# H_Bridge_AON6500.net
KiCad netlist of a schematic drawn in Altium Designer
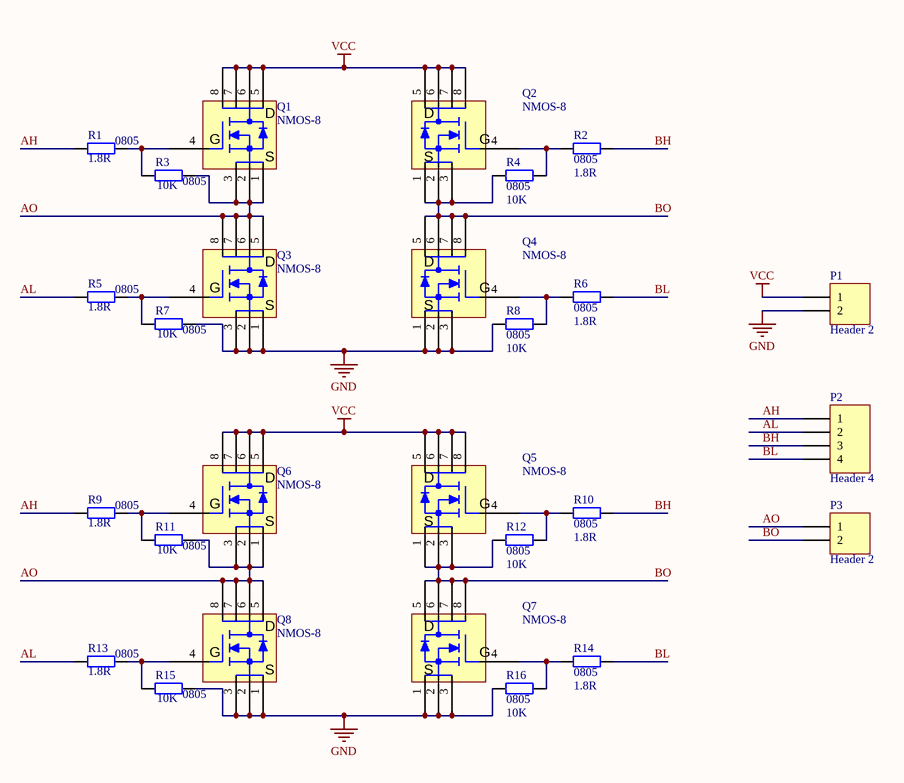
[diagram p0: H_Bridge_AON6500.SchDoc]

(export (version "E")
  (design (tool "Eeschema 10.0.6"))
  (components
    (comp (ref "P1")
      (value "Header 2")
      (footprint "HDR2.54-LI-2P")
      (description "Header, 2-Pin")
      (fields (field (name "PUBLISHER") "Altium Limited"))
      (libsource (lib "QT") (part "Header 2"))
    )
    (comp (ref "P2")
      (value "Header 4")
      (footprint "HDR2.54-LI-4P")
      (description "Header, 4-Pin")
      (fields (field (name "PUBLISHER") "Altium Limited"))
      (libsource (lib "QT") (part "Header 4"))
    )
    (comp (ref "P3")
      (value "Header 2")
      (footprint "HDR2.54-LI-2P")
      (description "Header, 2-Pin")
      (fields (field (name "PUBLISHER") "Altium Limited"))
      (libsource (lib "QT") (part "Header 2"))
    )
    (comp (ref "Q1") (value "NMOS-8") (footprint "PSOP8") (libsource (lib "") (part "NMOS-8_1")))
    (comp (ref "Q2") (value "NMOS-8") (footprint "PSOP8") (libsource (lib "常用元件库") (part "NMOS-8")))
    (comp (ref "Q3") (value "NMOS-8") (footprint "PSOP8") (libsource (lib "") (part "NMOS-8_1")))
    (comp (ref "Q4") (value "NMOS-8") (footprint "PSOP8") (libsource (lib "常用元件库") (part "NMOS-8")))
    (comp (ref "Q5") (value "NMOS-8") (footprint "PSOP8") (libsource (lib "常用元件库") (part "NMOS-8")))
    (comp (ref "Q6") (value "NMOS-8") (footprint "PSOP8") (libsource (lib "") (part "NMOS-8_1")))
    (comp (ref "Q7") (value "NMOS-8") (footprint "PSOP8") (libsource (lib "常用元件库") (part "NMOS-8")))
    (comp (ref "Q8") (value "NMOS-8") (footprint "PSOP8") (libsource (lib "") (part "NMOS-8_1")))
    (comp (ref "R1")
      (value "0805")
      (footprint "R 0805_L")
      (description "Resistor")
      (fields (field (name "ALTIUM_VALUE") "1.8R") (field (name "PUBLISHER") "Altium Limited"))
      (libsource (lib "QT") (part "RES2"))
    )
    (comp (ref "R2")
      (value "0805")
      (footprint "R 0805_L")
      (description "Resistor")
      (fields (field (name "ALTIUM_VALUE") "1.8R") (field (name "PUBLISHER") "Altium Limited"))
      (libsource (lib "") (part "RES2_1"))
    )
    (comp (ref "R3")
      (value "0805")
      (footprint "R 0805_L")
      (description "Resistor")
      (fields (field (name "ALTIUM_VALUE") "10K") (field (name "PUBLISHER") "Altium Limited"))
      (libsource (lib "QT") (part "RES2"))
    )
    (comp (ref "R4")
      (value "0805")
      (footprint "R 0805_L")
      (description "Resistor")
      (fields (field (name "ALTIUM_VALUE") "10K") (field (name "PUBLISHER") "Altium Limited"))
      (libsource (lib "") (part "RES2_1"))
    )
    (comp (ref "R5")
      (value "0805")
      (footprint "R 0805_L")
      (description "Resistor")
      (fields (field (name "ALTIUM_VALUE") "1.8R") (field (name "PUBLISHER") "Altium Limited"))
      (libsource (lib "QT") (part "RES2"))
    )
    (comp (ref "R6")
      (value "0805")
      (footprint "R 0805_L")
      (description "Resistor")
      (fields (field (name "ALTIUM_VALUE") "1.8R") (field (name "PUBLISHER") "Altium Limited"))
      (libsource (lib "") (part "RES2_1"))
    )
    (comp (ref "R7")
      (value "0805")
      (footprint "R 0805_L")
      (description "Resistor")
      (fields (field (name "ALTIUM_VALUE") "10K") (field (name "PUBLISHER") "Altium Limited"))
      (libsource (lib "QT") (part "RES2"))
    )
    (comp (ref "R8")
      (value "0805")
      (footprint "R 0805_L")
      (description "Resistor")
      (fields (field (name "ALTIUM_VALUE") "10K") (field (name "PUBLISHER") "Altium Limited"))
      (libsource (lib "") (part "RES2_1"))
    )
    (comp (ref "R9")
      (value "0805")
      (footprint "R 0805_L")
      (description "Resistor")
      (fields (field (name "ALTIUM_VALUE") "1.8R") (field (name "PUBLISHER") "Altium Limited"))
      (libsource (lib "QT") (part "RES2"))
    )
    (comp (ref "R10")
      (value "0805")
      (footprint "R 0805_L")
      (description "Resistor")
      (fields (field (name "ALTIUM_VALUE") "1.8R") (field (name "PUBLISHER") "Altium Limited"))
      (libsource (lib "") (part "RES2_1"))
    )
    (comp (ref "R11")
      (value "0805")
      (footprint "R 0805_L")
      (description "Resistor")
      (fields (field (name "ALTIUM_VALUE") "10K") (field (name "PUBLISHER") "Altium Limited"))
      (libsource (lib "QT") (part "RES2"))
    )
    (comp (ref "R12")
      (value "0805")
      (footprint "R 0805_L")
      (description "Resistor")
      (fields (field (name "ALTIUM_VALUE") "10K") (field (name "PUBLISHER") "Altium Limited"))
      (libsource (lib "") (part "RES2_1"))
    )
    (comp (ref "R13")
      (value "0805")
      (footprint "R 0805_L")
      (description "Resistor")
      (fields (field (name "ALTIUM_VALUE") "1.8R") (field (name "PUBLISHER") "Altium Limited"))
      (libsource (lib "QT") (part "RES2"))
    )
    (comp (ref "R14")
      (value "0805")
      (footprint "R 0805_L")
      (description "Resistor")
      (fields (field (name "ALTIUM_VALUE") "1.8R") (field (name "PUBLISHER") "Altium Limited"))
      (libsource (lib "") (part "RES2_1"))
    )
    (comp (ref "R15")
      (value "0805")
      (footprint "R 0805_L")
      (description "Resistor")
      (fields (field (name "ALTIUM_VALUE") "10K") (field (name "PUBLISHER") "Altium Limited"))
      (libsource (lib "QT") (part "RES2"))
    )
    (comp (ref "R16")
      (value "0805")
      (footprint "R 0805_L")
      (description "Resistor")
      (fields (field (name "ALTIUM_VALUE") "10K") (field (name "PUBLISHER") "Altium Limited"))
      (libsource (lib "") (part "RES2_1"))
    )
  )
  (nets
    (net (code "1") (name "/AH") (class "Default")
      (node (ref "P2") (pin "1") (pinfunction "1_1") (pintype "passive"))
      (node (ref "R1") (pin "1") (pinfunction "1_1") (pintype "passive"))
      (node (ref "R9") (pin "1") (pinfunction "1_1") (pintype "passive"))
    )
    (net (code "2") (name "/AL") (class "Default")
      (node (ref "P2") (pin "2") (pinfunction "2_2") (pintype "passive"))
      (node (ref "R13") (pin "1") (pinfunction "1_1") (pintype "passive"))
      (node (ref "R5") (pin "1") (pinfunction "1_1") (pintype "passive"))
    )
    (net (code "3") (name "/AO") (class "Default")
      (node (ref "P3") (pin "1") (pinfunction "1_1") (pintype "passive"))
      (node (ref "Q1") (pin "1") (pinfunction "S_1") (pintype "passive"))
      (node (ref "Q1") (pin "2") (pinfunction "S_2") (pintype "passive"))
      (node (ref "Q1") (pin "3") (pinfunction "S_3") (pintype "passive"))
      (node (ref "Q3") (pin "5") (pinfunction "5_5") (pintype "passive"))
      (node (ref "Q3") (pin "6") (pinfunction "6_6") (pintype "passive"))
      (node (ref "Q3") (pin "7") (pinfunction "7_7") (pintype "passive"))
      (node (ref "Q3") (pin "8") (pinfunction "8_8") (pintype "passive"))
      (node (ref "Q6") (pin "1") (pinfunction "S_1") (pintype "passive"))
      (node (ref "Q6") (pin "2") (pinfunction "S_2") (pintype "passive"))
      (node (ref "Q6") (pin "3") (pinfunction "S_3") (pintype "passive"))
      (node (ref "Q8") (pin "5") (pinfunction "5_5") (pintype "passive"))
      (node (ref "Q8") (pin "6") (pinfunction "6_6") (pintype "passive"))
      (node (ref "Q8") (pin "7") (pinfunction "7_7") (pintype "passive"))
      (node (ref "Q8") (pin "8") (pinfunction "8_8") (pintype "passive"))
      (node (ref "R11") (pin "2") (pinfunction "2_2") (pintype "passive"))
      (node (ref "R3") (pin "2") (pinfunction "2_2") (pintype "passive"))
    )
    (net (code "4") (name "/BH") (class "Default")
      (node (ref "P2") (pin "3") (pinfunction "3_3") (pintype "passive"))
      (node (ref "R10") (pin "1") (pinfunction "1_1") (pintype "passive"))
      (node (ref "R2") (pin "1") (pinfunction "1_1") (pintype "passive"))
    )
    (net (code "5") (name "/BL") (class "Default")
      (node (ref "P2") (pin "4") (pinfunction "4_4") (pintype "passive"))
      (node (ref "R14") (pin "1") (pinfunction "1_1") (pintype "passive"))
      (node (ref "R6") (pin "1") (pinfunction "1_1") (pintype "passive"))
    )
    (net (code "6") (name "/BO") (class "Default")
      (node (ref "P3") (pin "2") (pinfunction "2_2") (pintype "passive"))
      (node (ref "Q2") (pin "1") (pinfunction "S_1") (pintype "passive"))
      (node (ref "Q2") (pin "2") (pinfunction "S_2") (pintype "passive"))
      (node (ref "Q2") (pin "3") (pinfunction "S_3") (pintype "passive"))
      (node (ref "Q4") (pin "5") (pinfunction "5_5") (pintype "passive"))
      (node (ref "Q4") (pin "6") (pinfunction "6_6") (pintype "passive"))
      (node (ref "Q4") (pin "7") (pinfunction "7_7") (pintype "passive"))
      (node (ref "Q4") (pin "8") (pinfunction "8_8") (pintype "passive"))
      (node (ref "Q5") (pin "1") (pinfunction "S_1") (pintype "passive"))
      (node (ref "Q5") (pin "2") (pinfunction "S_2") (pintype "passive"))
      (node (ref "Q5") (pin "3") (pinfunction "S_3") (pintype "passive"))
      (node (ref "Q7") (pin "5") (pinfunction "5_5") (pintype "passive"))
      (node (ref "Q7") (pin "6") (pinfunction "6_6") (pintype "passive"))
      (node (ref "Q7") (pin "7") (pinfunction "7_7") (pintype "passive"))
      (node (ref "Q7") (pin "8") (pinfunction "8_8") (pintype "passive"))
      (node (ref "R12") (pin "2") (pinfunction "2_2") (pintype "passive"))
      (node (ref "R4") (pin "2") (pinfunction "2_2") (pintype "passive"))
    )
    (net (code "7") (name "GND") (class "Default")
      (node (ref "P1") (pin "2") (pinfunction "2_2") (pintype "passive"))
      (node (ref "Q3") (pin "1") (pinfunction "S_1") (pintype "passive"))
      (node (ref "Q3") (pin "2") (pinfunction "S_2") (pintype "passive"))
      (node (ref "Q3") (pin "3") (pinfunction "S_3") (pintype "passive"))
      (node (ref "Q4") (pin "1") (pinfunction "S_1") (pintype "passive"))
      (node (ref "Q4") (pin "2") (pinfunction "S_2") (pintype "passive"))
      (node (ref "Q4") (pin "3") (pinfunction "S_3") (pintype "passive"))
      (node (ref "Q7") (pin "1") (pinfunction "S_1") (pintype "passive"))
      (node (ref "Q7") (pin "2") (pinfunction "S_2") (pintype "passive"))
      (node (ref "Q7") (pin "3") (pinfunction "S_3") (pintype "passive"))
      (node (ref "Q8") (pin "1") (pinfunction "S_1") (pintype "passive"))
      (node (ref "Q8") (pin "2") (pinfunction "S_2") (pintype "passive"))
      (node (ref "Q8") (pin "3") (pinfunction "S_3") (pintype "passive"))
      (node (ref "R15") (pin "2") (pinfunction "2_2") (pintype "passive"))
      (node (ref "R16") (pin "2") (pinfunction "2_2") (pintype "passive"))
      (node (ref "R7") (pin "2") (pinfunction "2_2") (pintype "passive"))
      (node (ref "R8") (pin "2") (pinfunction "2_2") (pintype "passive"))
    )
    (net (code "8") (name "Net-(Q1-G)") (class "Default")
      (node (ref "Q1") (pin "4") (pinfunction "G_4") (pintype "passive"))
      (node (ref "R1") (pin "2") (pinfunction "2_2") (pintype "passive"))
      (node (ref "R3") (pin "1") (pinfunction "1_1") (pintype "passive"))
    )
    (net (code "9") (name "Net-(Q2-G)") (class "Default")
      (node (ref "Q2") (pin "4") (pinfunction "G_4") (pintype "passive"))
      (node (ref "R2") (pin "2") (pinfunction "2_2") (pintype "passive"))
      (node (ref "R4") (pin "1") (pinfunction "1_1") (pintype "passive"))
    )
    (net (code "10") (name "Net-(Q3-G)") (class "Default")
      (node (ref "Q3") (pin "4") (pinfunction "G_4") (pintype "passive"))
      (node (ref "R5") (pin "2") (pinfunction "2_2") (pintype "passive"))
      (node (ref "R7") (pin "1") (pinfunction "1_1") (pintype "passive"))
    )
    (net (code "11") (name "Net-(Q4-G)") (class "Default")
      (node (ref "Q4") (pin "4") (pinfunction "G_4") (pintype "passive"))
      (node (ref "R6") (pin "2") (pinfunction "2_2") (pintype "passive"))
      (node (ref "R8") (pin "1") (pinfunction "1_1") (pintype "passive"))
    )
    (net (code "12") (name "Net-(Q5-G)") (class "Default")
      (node (ref "Q5") (pin "4") (pinfunction "G_4") (pintype "passive"))
      (node (ref "R10") (pin "2") (pinfunction "2_2") (pintype "passive"))
      (node (ref "R12") (pin "1") (pinfunction "1_1") (pintype "passive"))
    )
    (net (code "13") (name "Net-(Q6-G)") (class "Default")
      (node (ref "Q6") (pin "4") (pinfunction "G_4") (pintype "passive"))
      (node (ref "R11") (pin "1") (pinfunction "1_1") (pintype "passive"))
      (node (ref "R9") (pin "2") (pinfunction "2_2") (pintype "passive"))
    )
    (net (code "14") (name "Net-(Q7-G)") (class "Default")
      (node (ref "Q7") (pin "4") (pinfunction "G_4") (pintype "passive"))
      (node (ref "R14") (pin "2") (pinfunction "2_2") (pintype "passive"))
      (node (ref "R16") (pin "1") (pinfunction "1_1") (pintype "passive"))
    )
    (net (code "15") (name "Net-(Q8-G)") (class "Default")
      (node (ref "Q8") (pin "4") (pinfunction "G_4") (pintype "passive"))
      (node (ref "R13") (pin "2") (pinfunction "2_2") (pintype "passive"))
      (node (ref "R15") (pin "1") (pinfunction "1_1") (pintype "passive"))
    )
    (net (code "16") (name "VCC") (class "Default")
      (node (ref "P1") (pin "1") (pinfunction "1_1") (pintype "passive"))
      (node (ref "Q1") (pin "5") (pinfunction "5_5") (pintype "passive"))
      (node (ref "Q1") (pin "6") (pinfunction "6_6") (pintype "passive"))
      (node (ref "Q1") (pin "7") (pinfunction "7_7") (pintype "passive"))
      (node (ref "Q1") (pin "8") (pinfunction "8_8") (pintype "passive"))
      (node (ref "Q2") (pin "5") (pinfunction "5_5") (pintype "passive"))
      (node (ref "Q2") (pin "6") (pinfunction "6_6") (pintype "passive"))
      (node (ref "Q2") (pin "7") (pinfunction "7_7") (pintype "passive"))
      (node (ref "Q2") (pin "8") (pinfunction "8_8") (pintype "passive"))
      (node (ref "Q5") (pin "5") (pinfunction "5_5") (pintype "passive"))
      (node (ref "Q5") (pin "6") (pinfunction "6_6") (pintype "passive"))
      (node (ref "Q5") (pin "7") (pinfunction "7_7") (pintype "passive"))
      (node (ref "Q5") (pin "8") (pinfunction "8_8") (pintype "passive"))
      (node (ref "Q6") (pin "5") (pinfunction "5_5") (pintype "passive"))
      (node (ref "Q6") (pin "6") (pinfunction "6_6") (pintype "passive"))
      (node (ref "Q6") (pin "7") (pinfunction "7_7") (pintype "passive"))
      (node (ref "Q6") (pin "8") (pinfunction "8_8") (pintype "passive"))
    )
  )
)
